# controle_motor_alimentacao.net
KiCad netlist of a schematic drawn in Altium Designer
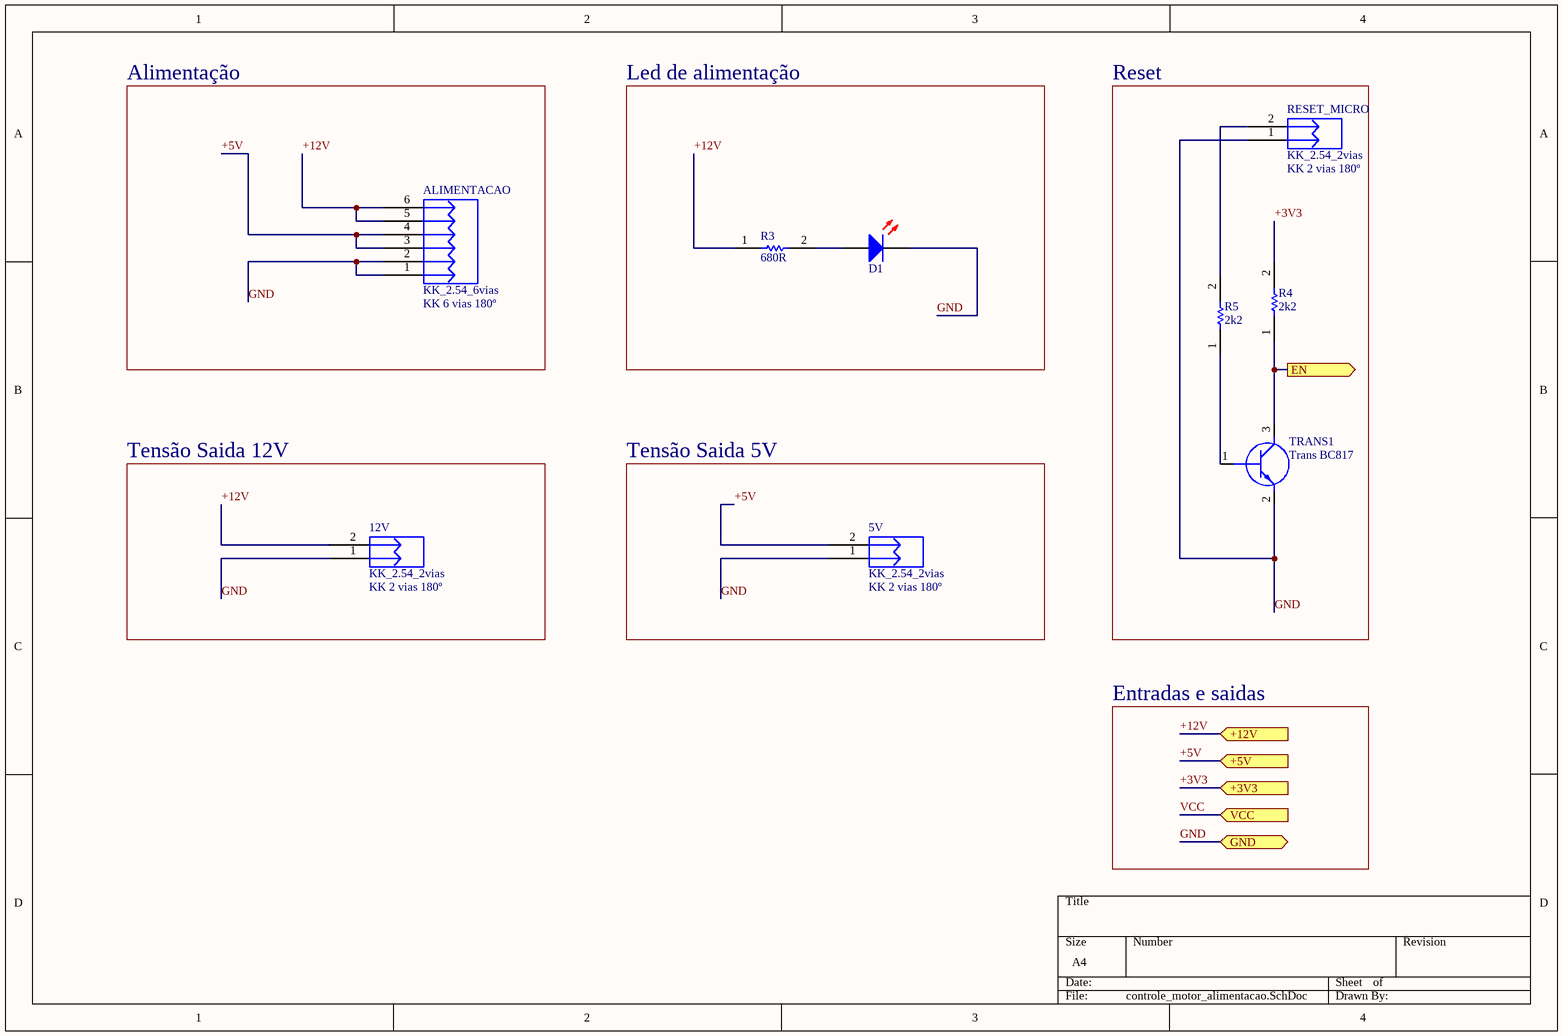
[diagram p0: controle_motor_alimentacao.SchDoc]

(export (version "E")
  (design (tool "Eeschema 10.0.6"))
  (components
    (comp (ref "5V")
      (value "KK_2.54_2vias")
      (footprint "KK_2VIAS_180º")
      (description "Conector KK 2.54mm 2 vias")
      (fields (field (name "VALOR") "KK 2 vias 180º"))
      (libsource (lib "Sinaliza玢o_Official") (part "KK_2.54_2vias"))
    )
    (comp (ref "12V")
      (value "KK_2.54_2vias")
      (footprint "KK_2VIAS_180º")
      (description "Conector KK 2.54mm 2 vias")
      (fields (field (name "VALOR") "KK 2 vias 180º"))
      (libsource (lib "Sinaliza玢o_Official") (part "KK_2.54_2vias"))
    )
    (comp (ref "ALIMENTACAO")
      (value "KK_2.54_6vias")
      (footprint "KK_6vias_180°")
      (description "Conector KK 2.54mm 6 vias")
      (fields (field (name "VALOR") "KK 6 vias 180º"))
      (libsource (lib "Conectores_Sch") (part "KK_2.54_6vias"))
    )
    (comp (ref "D1")
      (value "LED 3MM RED")
      (footprint "LED RED")
      (fields (field (name "MANUFACTURER") "Paralight") (field (name "MANUFACTURER PART NUMBER") "IMP585"))
      (libsource (lib "Sinaliza玢o_Official") (part "LED 3MM RED"))
    )
    (comp (ref "R3")
      (value "680R")
      (footprint "RESC3216X60N")
      (description "Resistor")
      (fields
        (field (name "MANUFACTURER_PART_NUMBER") "CRCW12064K70FKEA")
        (field (name "MOUSER PART NUMBER") "71-CRCW1206-4.7K-E3")
      )
      (libsource (lib "Sinaliza玢o_Official") (part "Resistor 1206"))
    )
    (comp (ref "R4")
      (value "2k2")
      (footprint "RESC3216X60N")
      (description "Resistor")
      (fields
        (field (name "MANUFACTURER_PART_NUMBER") "CRCW12064K70FKEA")
        (field (name "MOUSER PART NUMBER") "71-CRCW1206-4.7K-E3")
      )
      (libsource (lib "Sinaliza玢o_Official") (part "Resistor 1206"))
    )
    (comp (ref "R5")
      (value "2k2")
      (footprint "RESC3216X60N")
      (description "Resistor")
      (fields
        (field (name "MANUFACTURER_PART_NUMBER") "CRCW12064K70FKEA")
        (field (name "MOUSER PART NUMBER") "71-CRCW1206-4.7K-E3")
      )
      (libsource (lib "Sinaliza玢o_Official") (part "Resistor 1206"))
    )
    (comp (ref "RESET_MICRO")
      (value "KK_2.54_2vias")
      (footprint "KK_2VIAS_180º")
      (description "Conector KK 2.54mm 2 vias")
      (fields (field (name "VALOR") "KK 2 vias 180º"))
      (libsource (lib "Sinaliza玢o_Official") (part "KK_2.54_2vias"))
    )
    (comp (ref "TRANS1")
      (value "Trans BC817")
      (footprint "SOT96P240X110-3N")
      (description "Transistor BJT NPN BC817-25-7-F")
      (fields
        (field (name "MANUFACTURER_PART_NUMBER") "BC817-25-7-F")
        (field (name "MOUSER PART NUMBER") "621-BC817-25-7-F")
      )
      (libsource (lib "Sinaliza玢o_Official") (part "Trans BC817"))
    )
  )
  (nets
    (net (code "1") (name "/+3V3") (class "Default")
      (node (ref "R4") (pin "2") (pinfunction "2_2") (pintype "passive"))
    )
    (net (code "2") (name "/+5V") (class "Default")
      (node (ref "5V") (pin "2") (pintype "passive"))
      (node (ref "ALIMENTACAO") (pin "3") (pintype "passive"))
      (node (ref "ALIMENTACAO") (pin "4") (pintype "passive"))
    )
    (net (code "3") (name "/+12V") (class "Default")
      (node (ref "12V") (pin "2") (pintype "passive"))
      (node (ref "ALIMENTACAO") (pin "5") (pintype "passive"))
      (node (ref "ALIMENTACAO") (pin "6") (pintype "passive"))
      (node (ref "R3") (pin "1") (pinfunction "1_1") (pintype "passive"))
    )
    (net (code "4") (name "/EN") (class "Default")
      (node (ref "R4") (pin "1") (pinfunction "1_1") (pintype "passive"))
      (node (ref "TRANS1") (pin "3") (pinfunction "C_3") (pintype "passive"))
    )
    (net (code "5") (name "/GND") (class "Default")
      (node (ref "12V") (pin "1") (pintype "passive"))
      (node (ref "5V") (pin "1") (pintype "passive"))
      (node (ref "ALIMENTACAO") (pin "1") (pintype "passive"))
      (node (ref "ALIMENTACAO") (pin "2") (pintype "passive"))
      (node (ref "D1") (pin "2") (pinfunction "K_2") (pintype "passive"))
      (node (ref "RESET_MICRO") (pin "1") (pintype "passive"))
      (node (ref "TRANS1") (pin "2") (pinfunction "E_2") (pintype "passive"))
    )
    (net (code "7") (name "Net-(D1-A)") (class "Default")
      (node (ref "D1") (pin "1") (pinfunction "A_1") (pintype "passive"))
      (node (ref "R3") (pin "2") (pinfunction "2_2") (pintype "passive"))
    )
    (net (code "8") (name "Net-(R5-Pad2)") (class "Default")
      (node (ref "R5") (pin "2") (pinfunction "2_2") (pintype "passive"))
      (node (ref "RESET_MICRO") (pin "2") (pintype "passive"))
    )
    (net (code "9") (name "Net-(TRANS1-B)") (class "Default")
      (node (ref "R5") (pin "1") (pinfunction "1_1") (pintype "passive"))
      (node (ref "TRANS1") (pin "1") (pinfunction "B_1") (pintype "passive"))
    )
  )
)
